# Power_CAN.net
KiCad netlist of a schematic drawn in Altium Designer
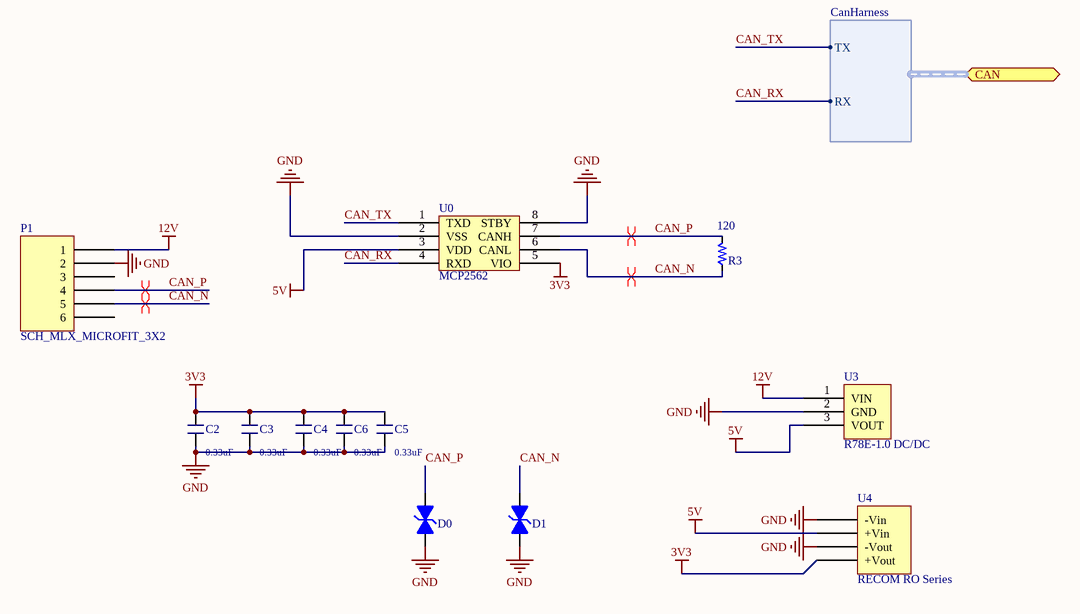
[diagram p0: Power&CAN.SchDoc]

(export (version "E")
  (design (tool "Eeschema 10.0.6"))
  (components
    (comp (ref "C2")
      (value "SCH_GENERIC_CAPACITOR_0603")
      (footprint "PCB_GENERIC_SMD_0603")
      (description "Generic SMD capacitor 0603")
      (fields (field (name "TOLERANCE") "*%") (field (name "CAPACITANCE") "0.33uF"))
      (libsource (lib "Generic 0603 Capacitor") (part "SCH_GENERIC_CAPACITOR_0603"))
    )
    (comp (ref "C3")
      (value "SCH_GENERIC_CAPACITOR_0603")
      (footprint "PCB_GENERIC_SMD_0603")
      (description "Generic SMD capacitor 0603")
      (fields (field (name "TOLERANCE") "*%") (field (name "CAPACITANCE") "0.33uF"))
      (libsource (lib "Generic 0603 Capacitor") (part "SCH_GENERIC_CAPACITOR_0603"))
    )
    (comp (ref "C4")
      (value "SCH_GENERIC_CAPACITOR_0603")
      (footprint "PCB_GENERIC_SMD_0603")
      (description "Generic SMD capacitor 0603")
      (fields (field (name "TOLERANCE") "*%") (field (name "CAPACITANCE") "0.33uF"))
      (libsource (lib "Generic 0603 Capacitor") (part "SCH_GENERIC_CAPACITOR_0603"))
    )
    (comp (ref "C5")
      (value "SCH_GENERIC_CAPACITOR_0603")
      (footprint "PCB_GENERIC_SMD_0603")
      (description "Generic SMD capacitor 0603")
      (fields (field (name "TOLERANCE") "*%") (field (name "CAPACITANCE") "0.33uF"))
      (libsource (lib "Generic 0603 Capacitor") (part "SCH_GENERIC_CAPACITOR_0603"))
    )
    (comp (ref "C6")
      (value "SCH_GENERIC_CAPACITOR_0603")
      (footprint "PCB_GENERIC_SMD_0603")
      (description "Generic SMD capacitor 0603")
      (fields (field (name "TOLERANCE") "*%") (field (name "CAPACITANCE") "0.33uF"))
      (libsource (lib "Generic 0603 Capacitor") (part "SCH_GENERIC_CAPACITOR_0603"))
    )
    (comp (ref "D0")
      (value "Bourns TVS Diode 3.3V SOD323")
      (footprint "TVS Diode SOD-323")
      (description "TVS DIODE 3.3VWM 10.9VC SOD323")
      (libsource (lib "TVS Diode 3V3") (part "Bourns TVS Diode 3.3V SOD323"))
    )
    (comp (ref "D1")
      (value "Bourns TVS Diode 3.3V SOD323")
      (footprint "TVS Diode SOD-323")
      (description "TVS DIODE 3.3VWM 10.9VC SOD323")
      (libsource (lib "TVS Diode 3V3") (part "Bourns TVS Diode 3.3V SOD323"))
    )
    (comp (ref "P1")
      (value "SCH_MLX_MICROFIT_3X2")
      (footprint "PCB_MLX_MICROFIT_3X2")
      (libsource (lib "Molex Microfit 3.0 3x2") (part "SCH_MLX_MICROFIT_3X2"))
    )
    (comp (ref "R3")
      (value "SCH_GENERIC_RESISTOR_0603")
      (footprint "PCB_GENERIC_SMD_0603")
      (description "Generic SMD resistor 0603")
      (fields (field (name "RESISTANCE") "120"))
      (libsource (lib "Generic 0603 Resistor") (part "SCH_GENERIC_RESISTOR_0603"))
    )
    (comp (ref "U0")
      (value "MCP2562")
      (footprint "SOIC127P600X175-8N")
      (description "1/1 Transceiver Full CAN 8-SOIC")
      (libsource (lib "Microchip MCP2562") (part "MCP2562"))
    )
    (comp (ref "U3")
      (value "R78E-1.0 DC/DC")
      (footprint "R78-1.0")
      (libsource (lib "Recom R78E-1.0") (part "R78E-1.0"))
    )
    (comp (ref "U4")
      (value "RECOM RO Series")
      (footprint "RECOM RO Series 1W DCDC")
      (libsource (lib "RECOM RO Series 1W DCDC") (part "RECOM RO Series DCDC Converter"))
    )
  )
  (nets
    (net (code "2") (name "/CAN_N") (class "Default")
      (node (ref "D1") (pin "1") (pinfunction "1_1") (pintype "passive"))
      (node (ref "P1") (pin "5") (pinfunction "5_5") (pintype "passive"))
      (node (ref "R3") (pin "1") (pinfunction "1_1") (pintype "passive"))
      (node (ref "U0") (pin "6") (pinfunction "CANL_6") (pintype "passive"))
    )
    (net (code "3") (name "/CAN_P") (class "Default")
      (node (ref "D0") (pin "1") (pinfunction "1_1") (pintype "passive"))
      (node (ref "P1") (pin "4") (pinfunction "4_4") (pintype "passive"))
      (node (ref "R3") (pin "2") (pinfunction "2_2") (pintype "passive"))
      (node (ref "U0") (pin "7") (pinfunction "CANH_7") (pintype "passive"))
    )
    (net (code "4") (name "/CAN_RX") (class "Default")
      (node (ref "U0") (pin "4") (pinfunction "RXD_4") (pintype "passive"))
    )
    (net (code "5") (name "/CAN_TX") (class "Default")
      (node (ref "U0") (pin "1") (pinfunction "TXD_1") (pintype "passive"))
    )
    (net (code "7") (name "3V3") (class "Default")
      (node (ref "C2") (pin "2") (pinfunction "2_2") (pintype "passive"))
      (node (ref "C3") (pin "2") (pinfunction "2_2") (pintype "passive"))
      (node (ref "C4") (pin "2") (pinfunction "2_2") (pintype "passive"))
      (node (ref "C5") (pin "2") (pinfunction "2_2") (pintype "passive"))
      (node (ref "C6") (pin "2") (pinfunction "2_2") (pintype "passive"))
      (node (ref "U0") (pin "5") (pinfunction "VIO_5") (pintype "passive"))
      (node (ref "U4") (pin "4") (pinfunction "+Vout_4") (pintype "passive"))
    )
    (net (code "8") (name "5V") (class "Default")
      (node (ref "U0") (pin "3") (pinfunction "VDD_3") (pintype "passive"))
      (node (ref "U3") (pin "3") (pinfunction "VOUT_3") (pintype "passive"))
      (node (ref "U4") (pin "2") (pinfunction "+Vin_2") (pintype "passive"))
    )
    (net (code "9") (name "12V") (class "Default")
      (node (ref "P1") (pin "1") (pinfunction "1_1") (pintype "passive"))
      (node (ref "U3") (pin "1") (pinfunction "VIN_1") (pintype "passive"))
    )
    (net (code "10") (name "GND") (class "Default")
      (node (ref "C2") (pin "1") (pinfunction "1_1") (pintype "passive"))
      (node (ref "C3") (pin "1") (pinfunction "1_1") (pintype "passive"))
      (node (ref "C4") (pin "1") (pinfunction "1_1") (pintype "passive"))
      (node (ref "C5") (pin "1") (pinfunction "1_1") (pintype "passive"))
      (node (ref "C6") (pin "1") (pinfunction "1_1") (pintype "passive"))
      (node (ref "D0") (pin "2") (pinfunction "2_2") (pintype "passive"))
      (node (ref "D1") (pin "2") (pinfunction "2_2") (pintype "passive"))
      (node (ref "P1") (pin "2") (pinfunction "2_2") (pintype "passive"))
      (node (ref "U0") (pin "2") (pinfunction "VSS_2") (pintype "passive"))
      (node (ref "U0") (pin "8") (pinfunction "STBY_8") (pintype "passive"))
      (node (ref "U3") (pin "2") (pinfunction "GND_2") (pintype "passive"))
      (node (ref "U4") (pin "1") (pinfunction "-Vin_1") (pintype "passive"))
      (node (ref "U4") (pin "3") (pinfunction "-Vout_3") (pintype "passive"))
    )
    (net (code "11") (name "unconnected-(P1-Pad3)") (class "Default")
      (node (ref "P1") (pin "3") (pinfunction "3_3") (pintype "passive"))
    )
    (net (code "12") (name "unconnected-(P1-Pad6)") (class "Default")
      (node (ref "P1") (pin "6") (pinfunction "6_6") (pintype "passive"))
    )
  )
)
